# 1V8_LDO.net
KiCad netlist of a schematic drawn in Altium Designer
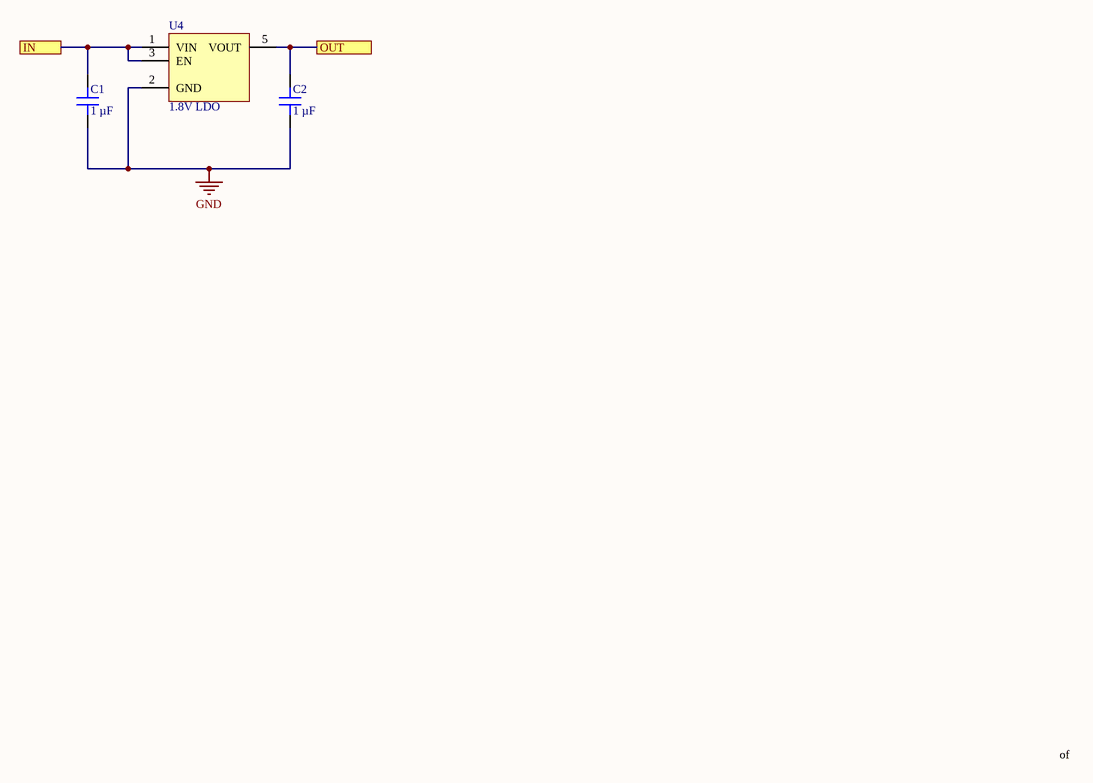
[diagram p0: 1V8_LDO.SchDoc]

(export (version "E")
  (design (tool "Eeschema 10.0.6"))
  (components
    (comp (ref "C1")
      (value "1 µF")
      (footprint "CAP 0402_1005")
      (description "CAP CER 0.1UF 16V X7R 0402")
      (fields (field (name "PART NUMBER") "C0402C104K4RACAUTO") (field (name "MANUFACTURER") "KEMET"))
      (libsource (lib "Celestial Altium Library - altium_library") (part "Capacitor"))
    )
    (comp (ref "C2")
      (value "1 µF")
      (footprint "CAP 0402_1005")
      (description "CAP CER 0.1UF 16V X7R 0402")
      (fields (field (name "PART NUMBER") "C0402C104K4RACAUTO") (field (name "MANUFACTURER") "KEMET"))
      (libsource (lib "Celestial Altium Library - altium_library") (part "Capacitor"))
    )
    (comp (ref "U4")
      (value "1.8V LDO")
      (footprint "TI SOT-23-5 DBV")
      (libsource (lib "IC") (part "MIC5504-1.8YM5"))
    )
  )
  (nets
    (net (code "1") (name "/IN") (class "Default")
      (node (ref "C1") (pin "2") (pinfunction "2_2") (pintype "passive"))
      (node (ref "U4") (pin "1") (pinfunction "VIN_1") (pintype "passive"))
      (node (ref "U4") (pin "3") (pinfunction "EN_3") (pintype "passive"))
    )
    (net (code "2") (name "/OUT") (class "Default")
      (node (ref "C2") (pin "2") (pinfunction "2_2") (pintype "passive"))
      (node (ref "U4") (pin "5") (pinfunction "VOUT_5") (pintype "passive"))
    )
    (net (code "3") (name "GND") (class "Default")
      (node (ref "C1") (pin "1") (pinfunction "1_1") (pintype "passive"))
      (node (ref "C2") (pin "1") (pinfunction "1_1") (pintype "passive"))
      (node (ref "U4") (pin "2") (pinfunction "GND_2") (pintype "passive"))
    )
  )
)
